# pow3_5e2.net
KiCad netlist of a schematic drawn in EAGLE
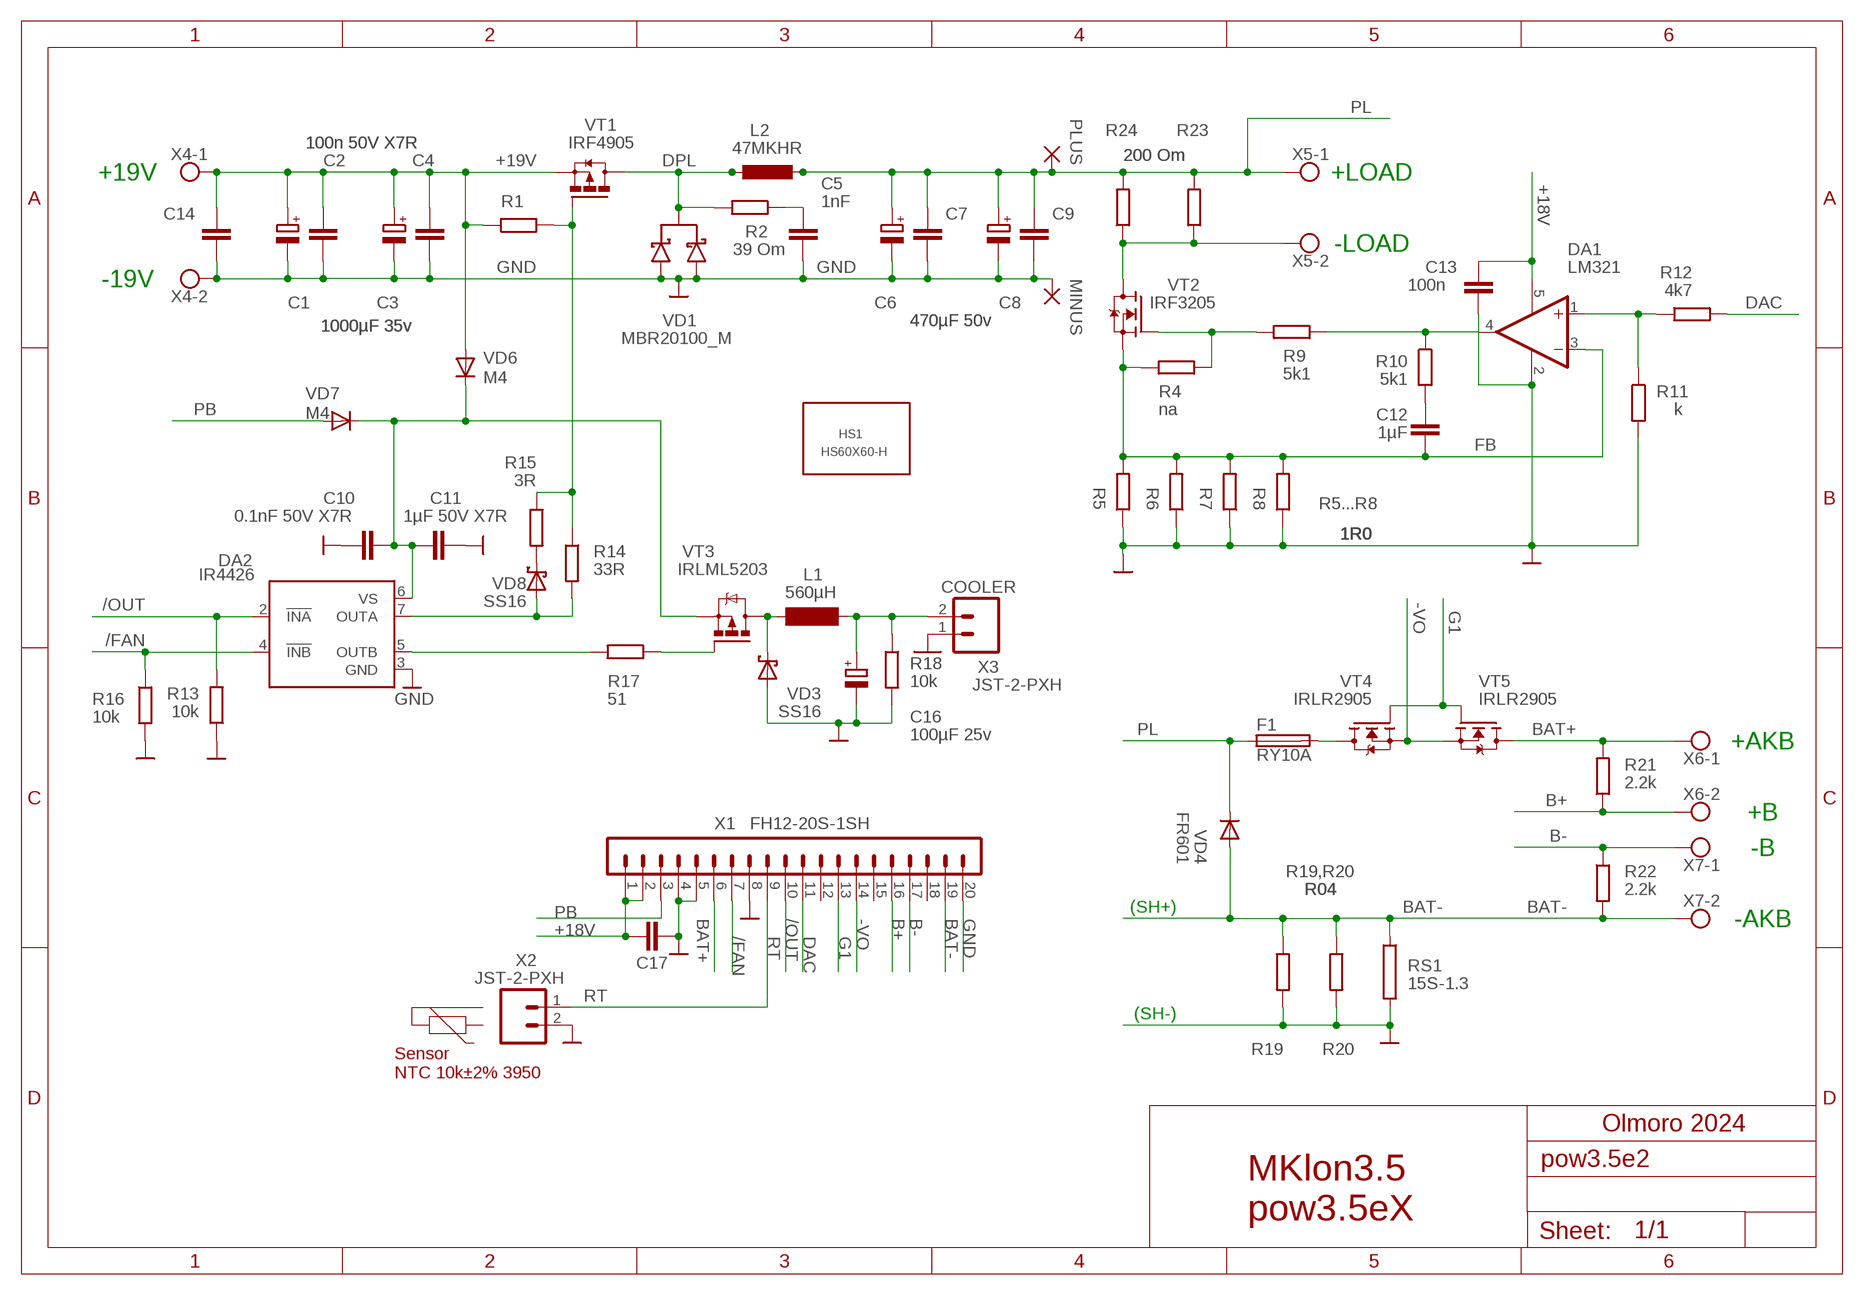
[diagram p0: schematic, sheet 1]

(export (version "E")
  (design (tool "Eeschema 10.0.6"))
  (components
    (comp (ref "C1")
      (value "1000µF 35v")
      (footprint "eagle-import:E5-10,5")
      (libsource (lib "eagle-import") (part "CPOL-EUE5-10.5"))
    )
    (comp (ref "C2")
      (value "100n 50V X7R")
      (footprint "eagle-import:C0805")
      (libsource (lib "eagle-import") (part "C-EUC0805"))
    )
    (comp (ref "C3")
      (value "1000µF 35v")
      (footprint "eagle-import:E5-10,5")
      (libsource (lib "eagle-import") (part "CPOL-EUE5-10.5"))
    )
    (comp (ref "C4")
      (value "100n 50V X7R")
      (footprint "eagle-import:C0805")
      (libsource (lib "eagle-import") (part "C-EUC0805"))
    )
    (comp (ref "C5")
      (value "1nF")
      (footprint "eagle-import:C075-042X103")
      (libsource (lib "eagle-import") (part "C-EU075-042X103"))
    )
    (comp (ref "C6")
      (value "470µF 50v")
      (footprint "eagle-import:E5-10,5")
      (libsource (lib "eagle-import") (part "CPOL-EUE5-10.5"))
    )
    (comp (ref "C7")
      (value "1mkF 50V X7R")
      (footprint "eagle-import:C0805")
      (libsource (lib "eagle-import") (part "C-EUC0805"))
    )
    (comp (ref "C8")
      (value "470µF 50v")
      (footprint "eagle-import:E5-10,5")
      (libsource (lib "eagle-import") (part "CPOL-EUE5-10.5"))
    )
    (comp (ref "C9")
      (value "1mkF 50V X7R")
      (footprint "eagle-import:C0805")
      (libsource (lib "eagle-import") (part "C-EUC0805"))
    )
    (comp (ref "C10")
      (value "0.1nF 50V X7R")
      (footprint "eagle-import:C0805")
      (libsource (lib "eagle-import") (part "C-EUC0805"))
    )
    (comp (ref "C11")
      (value "1µF 50V X7R")
      (footprint "eagle-import:C0805")
      (libsource (lib "eagle-import") (part "C-EUC0805"))
    )
    (comp (ref "C12")
      (value "1µF")
      (footprint "eagle-import:C0805")
      (libsource (lib "eagle-import") (part "C-EUC0805"))
    )
    (comp (ref "C13")
      (value "100n")
      (footprint "eagle-import:C0805")
      (libsource (lib "eagle-import") (part "C-EUC0805"))
    )
    (comp (ref "C14")
      (value "1mkF 50V X7R")
      (footprint "eagle-import:C0805")
      (libsource (lib "eagle-import") (part "C-EUC0805"))
    )
    (comp (ref "C16")
      (value "100µF 25v")
      (footprint "eagle-import:E5-6")
      (libsource (lib "eagle-import") (part "CPOL-EUE5-6"))
    )
    (comp (ref "C17")
      (value "C-EUC0805")
      (footprint "eagle-import:C0805")
      (libsource (lib "eagle-import") (part "C-EUC0805"))
    )
    (comp (ref "DA1")
      (value "LM321")
      (footprint "eagle-import:SOT23-5")
      (libsource (lib "eagle-import") (part "LM321?MF"))
    )
    (comp (ref "DA2")
      (value "IR4426")
      (footprint "eagle-import:DIL08")
      (fields (field (name "MF") "INTERNATIONAL RECTIFIER(IR)") (field (name "MPN") "IR4426PBF"))
      (libsource (lib "eagle-import") (part "IR4426"))
    )
    (comp (ref "F1")
      (value "RY10A")
      (footprint "eagle-import:RY10A")
      (libsource (lib "eagle-import") (part "RY10A"))
    )
    (comp (ref "HS1")
      (value "HS60X60-H")
      (footprint "eagle-import:HS60X60-H")
      (libsource (lib "eagle-import") (part "HS60X60-H"))
    )
    (comp (ref "L1")
      (value "560µH")
      (footprint "eagle-import:BS11")
      (libsource (lib "eagle-import") (part "BS11"))
    )
    (comp (ref "L2")
      (value "47MKHR")
      (footprint "eagle-import:47MKHR")
      (libsource (lib "eagle-import") (part "47MKHR"))
    )
    (comp (ref "MINUS")
      (value "3,81/1,4")
      (footprint "eagle-import:3,81_1,4")
      (libsource (lib "eagle-import") (part "3,81/1,4"))
    )
    (comp (ref "PLUS")
      (value "3,81/1,4")
      (footprint "eagle-import:3,81_1,4")
      (libsource (lib "eagle-import") (part "3,81/1,4"))
    )
    (comp (ref "R1")
      (value "R-EU_R1206")
      (footprint "eagle-import:R1206")
      (libsource (lib "eagle-import") (part "R-EU_R1206"))
    )
    (comp (ref "R2")
      (value "39 Om")
      (footprint "eagle-import:0414_15")
      (libsource (lib "eagle-import") (part "R-EU_0414/15"))
    )
    (comp (ref "R4")
      (value "na")
      (footprint "eagle-import:R1206")
      (libsource (lib "eagle-import") (part "R-EU_R1206"))
    )
    (comp (ref "R5")
      (value "1R0")
      (footprint "eagle-import:R2512")
      (libsource (lib "eagle-import") (part "R-EU_R2512"))
    )
    (comp (ref "R6")
      (value "1R0")
      (footprint "eagle-import:R2512")
      (libsource (lib "eagle-import") (part "R-EU_R2512"))
    )
    (comp (ref "R7")
      (value "1R0")
      (footprint "eagle-import:R2512")
      (libsource (lib "eagle-import") (part "R-EU_R2512"))
    )
    (comp (ref "R8")
      (value "1R0")
      (footprint "eagle-import:R2512")
      (libsource (lib "eagle-import") (part "R-EU_R2512"))
    )
    (comp (ref "R9")
      (value "5k1")
      (footprint "eagle-import:R0805")
      (libsource (lib "eagle-import") (part "R-EU_R0805"))
    )
    (comp (ref "R10")
      (value "5k1")
      (footprint "eagle-import:R0805")
      (libsource (lib "eagle-import") (part "R-EU_R0805"))
    )
    (comp (ref "R11")
      (value "k")
      (footprint "eagle-import:R0805")
      (libsource (lib "eagle-import") (part "R-EU_R0805"))
    )
    (comp (ref "R12")
      (value "4k7")
      (footprint "eagle-import:R0805")
      (libsource (lib "eagle-import") (part "R-EU_R0805"))
    )
    (comp (ref "R13")
      (value "10k")
      (footprint "eagle-import:R0805")
      (libsource (lib "eagle-import") (part "R-EU_R0805"))
    )
    (comp (ref "R14")
      (value "33R")
      (footprint "eagle-import:R1206")
      (libsource (lib "eagle-import") (part "R-EU_R1206"))
    )
    (comp (ref "R15")
      (value "3R")
      (footprint "eagle-import:R1206")
      (libsource (lib "eagle-import") (part "R-EU_R1206"))
    )
    (comp (ref "R16")
      (value "10k")
      (footprint "eagle-import:R0805")
      (libsource (lib "eagle-import") (part "R-EU_R0805"))
    )
    (comp (ref "R17")
      (value "51")
      (footprint "eagle-import:R0805")
      (libsource (lib "eagle-import") (part "R-EU_R0805"))
    )
    (comp (ref "R18")
      (value "10k")
      (footprint "eagle-import:R0805")
      (libsource (lib "eagle-import") (part "R-EU_R0805"))
    )
    (comp (ref "R19")
      (value "R04")
      (footprint "eagle-import:R2512")
      (libsource (lib "eagle-import") (part "R-EU_R2512"))
    )
    (comp (ref "R20")
      (value "R04")
      (footprint "eagle-import:R2512")
      (libsource (lib "eagle-import") (part "R-EU_R2512"))
    )
    (comp (ref "R21")
      (value "2.2k")
      (footprint "eagle-import:R1206")
      (libsource (lib "eagle-import") (part "R-EU_R1206"))
    )
    (comp (ref "R22")
      (value "2.2k")
      (footprint "eagle-import:R1206")
      (libsource (lib "eagle-import") (part "R-EU_R1206"))
    )
    (comp (ref "R23")
      (value "200 Om")
      (footprint "eagle-import:0414_15")
      (libsource (lib "eagle-import") (part "R-EU_0414/15"))
    )
    (comp (ref "R24")
      (value "200 Om")
      (footprint "eagle-import:0414_15")
      (libsource (lib "eagle-import") (part "R-EU_0414/15"))
    )
    (comp (ref "RS1")
      (value "15S-1.3")
      (footprint "eagle-import:15S-1.3")
      (libsource (lib "eagle-import") (part "15S-1.3"))
    )
    (comp (ref "VD1")
      (value "MBR20100_M")
      (footprint "eagle-import:TO220DLK")
      (libsource (lib "eagle-import") (part "MBR20100_M"))
    )
    (comp (ref "VD3")
      (value "SS16")
      (footprint "eagle-import:DO214AC")
      (libsource (lib "eagle-import") (part "SS16"))
    )
    (comp (ref "VD4")
      (value "FR601")
      (footprint "eagle-import:DIODE-1_P6-15")
      (libsource (lib "eagle-import") (part "DIODE-1_DIODE-P6-15"))
    )
    (comp (ref "VD6")
      (value "M4")
      (footprint "eagle-import:DO214AC")
      (libsource (lib "eagle-import") (part "DIODE-DO214AC"))
    )
    (comp (ref "VD7")
      (value "M4")
      (footprint "eagle-import:DO214AC")
      (libsource (lib "eagle-import") (part "DIODE-DO214AC"))
    )
    (comp (ref "VD8")
      (value "SS16")
      (footprint "eagle-import:DO214AC")
      (libsource (lib "eagle-import") (part "SS16"))
    )
    (comp (ref "VT1")
      (value "IRF4905")
      (footprint "eagle-import:TO-220FP_M")
      (libsource (lib "eagle-import") (part "IRFP9540N_M"))
    )
    (comp (ref "VT2")
      (value "IRF3205")
      (footprint "eagle-import:TO-220FP_M")
      (libsource (lib "eagle-import") (part "STP16NF06FP"))
    )
    (comp (ref "VT3")
      (value "IRLML5203")
      (footprint "eagle-import:MICRO3")
      (libsource (lib "eagle-import") (part "IRLML5203"))
    )
    (comp (ref "VT4")
      (value "IRLR2905")
      (footprint "eagle-import:TO252")
      (libsource (lib "eagle-import") (part "IRLR2905"))
    )
    (comp (ref "VT5")
      (value "IRLR2905")
      (footprint "eagle-import:TO252")
      (libsource (lib "eagle-import") (part "IRLR2905"))
    )
    (comp (ref "X1")
      (value "FH12-20S-1SH")
      (footprint "eagle-import:FH12-20S-1SH")
      (libsource (lib "eagle-import") (part "FH12-20S-1SH"))
    )
    (comp (ref "X2")
      (value "JST-2-PXH")
      (footprint "eagle-import:JST-2-PXH")
      (libsource (lib "eagle-import") (part "JST-2-PXH"))
    )
    (comp (ref "X3")
      (value "JST-2-PXH")
      (footprint "eagle-import:JST-2-PXH")
      (libsource (lib "eagle-import") (part "JST-2-PXH"))
    )
    (comp (ref "X4")
      (value "AK500/2")
      (footprint "eagle-import:AK500_2")
      (libsource (lib "eagle-import") (part "AK500/2"))
    )
    (comp (ref "X5")
      (value "AK500/2")
      (footprint "eagle-import:AK500_2")
      (libsource (lib "eagle-import") (part "AK500/2"))
    )
    (comp (ref "X6")
      (value "AK500/2")
      (footprint "eagle-import:AK500_2")
      (libsource (lib "eagle-import") (part "AK500/2"))
    )
    (comp (ref "X7")
      (value "AK500/2")
      (footprint "eagle-import:AK500_2")
      (libsource (lib "eagle-import") (part "AK500/2"))
    )
  )
  (nets
    (net (code "1") (name "/+18V") (class "Default")
      (node (ref "C13") (pin "2") (pinfunction "2_2") (pintype "passive"))
      (node (ref "C17") (pin "2") (pinfunction "2_2") (pintype "passive"))
      (node (ref "DA1") (pin "5") (pinfunction "V+_5") (pintype "power_in"))
      (node (ref "X1") (pin "1") (pinfunction "1_1") (pintype "passive"))
      (node (ref "X1") (pin "2") (pinfunction "2_2") (pintype "passive"))
    )
    (net (code "2") (name "/+19V") (class "Default")
      (node (ref "C1") (pin "+") (pinfunction "+_+") (pintype "passive"))
      (node (ref "C14") (pin "1") (pinfunction "1_1") (pintype "passive"))
      (node (ref "C2") (pin "2") (pinfunction "2_2") (pintype "passive"))
      (node (ref "C3") (pin "+") (pinfunction "+_+") (pintype "passive"))
      (node (ref "C4") (pin "2") (pinfunction "2_2") (pintype "passive"))
      (node (ref "R1") (pin "1") (pinfunction "1_1") (pintype "passive"))
      (node (ref "VD6") (pin "A") (pinfunction "A_A") (pintype "passive"))
      (node (ref "VT1") (pin "3") (pinfunction "S_3") (pintype "passive"))
      (node (ref "X4") (pin "1") (pinfunction "KL_1") (pintype "passive"))
    )
    (net (code "3") (name "/-VO") (class "Default")
      (node (ref "VT4") (pin "3") (pinfunction "S_3") (pintype "passive"))
      (node (ref "VT5") (pin "3") (pinfunction "S_3") (pintype "passive"))
      (node (ref "X1") (pin "14") (pinfunction "14_14") (pintype "passive"))
    )
    (net (code "4") (name "/B+") (class "Default")
      (node (ref "R21") (pin "1") (pinfunction "1_1") (pintype "passive"))
      (node (ref "X1") (pin "16") (pinfunction "16_16") (pintype "passive"))
      (node (ref "X6") (pin "2") (pinfunction "KL_2") (pintype "passive"))
    )
    (net (code "5") (name "/B-") (class "Default")
      (node (ref "R22") (pin "1") (pinfunction "1_1") (pintype "passive"))
      (node (ref "X1") (pin "17") (pinfunction "17_17") (pintype "passive"))
      (node (ref "X7") (pin "1") (pinfunction "KL_1") (pintype "passive"))
    )
    (net (code "6") (name "/BAT+") (class "Default")
      (node (ref "R21") (pin "2") (pinfunction "2_2") (pintype "passive"))
      (node (ref "VT5") (pin "4") (pinfunction "D_4") (pintype "passive"))
      (node (ref "X1") (pin "6") (pinfunction "6_6") (pintype "passive"))
      (node (ref "X6") (pin "1") (pinfunction "KL_1") (pintype "passive"))
    )
    (net (code "7") (name "/BAT-") (class "Default")
      (node (ref "R19") (pin "1") (pinfunction "1_1") (pintype "passive"))
      (node (ref "R20") (pin "1") (pinfunction "1_1") (pintype "passive"))
      (node (ref "R22") (pin "2") (pinfunction "2_2") (pintype "passive"))
      (node (ref "RS1") (pin "1") (pinfunction "1_1") (pintype "passive"))
      (node (ref "VD4") (pin "A") (pinfunction "A_A") (pintype "passive"))
      (node (ref "X1") (pin "19") (pinfunction "19_19") (pintype "passive"))
      (node (ref "X7") (pin "2") (pinfunction "KL_2") (pintype "passive"))
    )
    (net (code "8") (name "/COOLER") (class "Default")
      (node (ref "C16") (pin "+") (pinfunction "+_+") (pintype "passive"))
      (node (ref "L1") (pin "2") (pinfunction "2_2") (pintype "passive"))
      (node (ref "R18") (pin "1") (pinfunction "1_1") (pintype "passive"))
      (node (ref "X3") (pin "2") (pinfunction "2_2") (pintype "passive"))
    )
    (net (code "9") (name "/DAC") (class "Default")
      (node (ref "R12") (pin "2") (pinfunction "2_2") (pintype "passive"))
      (node (ref "X1") (pin "11") (pinfunction "11_11") (pintype "passive"))
    )
    (net (code "10") (name "/DPL") (class "Default")
      (node (ref "L2") (pin "1") (pinfunction "1_1") (pintype "passive"))
      (node (ref "L2") (pin "1@2") (pinfunction "1_1@2") (pintype "passive"))
      (node (ref "R2") (pin "2") (pinfunction "2_2") (pintype "passive"))
      (node (ref "VD1") (pin "2") (pinfunction "C_2") (pintype "passive"))
      (node (ref "VT1") (pin "2") (pinfunction "D_2") (pintype "passive"))
    )
    (net (code "11") (name "/FB") (class "Default")
      (node (ref "C12") (pin "2") (pinfunction "2_2") (pintype "passive"))
      (node (ref "DA1") (pin "3") (pinfunction "-IN_3") (pintype "input"))
      (node (ref "R4") (pin "1") (pinfunction "1_1") (pintype "passive"))
      (node (ref "R5") (pin "2") (pinfunction "2_2") (pintype "passive"))
      (node (ref "R6") (pin "2") (pinfunction "2_2") (pintype "passive"))
      (node (ref "R7") (pin "2") (pinfunction "2_2") (pintype "passive"))
      (node (ref "R8") (pin "2") (pinfunction "2_2") (pintype "passive"))
      (node (ref "VT2") (pin "3") (pinfunction "S_3") (pintype "passive"))
    )
    (net (code "12") (name "/G1") (class "Default")
      (node (ref "VT4") (pin "1") (pinfunction "G_1") (pintype "passive"))
      (node (ref "VT5") (pin "1") (pinfunction "G_1") (pintype "passive"))
      (node (ref "X1") (pin "13") (pinfunction "13_13") (pintype "passive"))
    )
    (net (code "13") (name "/PB") (class "Default")
      (node (ref "VD7") (pin "A") (pinfunction "A_A") (pintype "passive"))
      (node (ref "X1") (pin "3") (pinfunction "3_3") (pintype "passive"))
    )
    (net (code "14") (name "/PL") (class "Default")
      (node (ref "C6") (pin "+") (pinfunction "+_+") (pintype "passive"))
      (node (ref "C7") (pin "1") (pinfunction "1_1") (pintype "passive"))
      (node (ref "C8") (pin "+") (pinfunction "+_+") (pintype "passive"))
      (node (ref "C9") (pin "1") (pinfunction "1_1") (pintype "passive"))
      (node (ref "F1") (pin "1") (pinfunction "1_1") (pintype "passive"))
      (node (ref "L2") (pin "2@7") (pinfunction "2_2@7") (pintype "passive"))
      (node (ref "L2") (pin "2@8") (pinfunction "2_2@8") (pintype "passive"))
      (node (ref "PLUS") (pin "1") (pinfunction "P_1") (pintype "passive"))
      (node (ref "R23") (pin "2") (pinfunction "2_2") (pintype "passive"))
      (node (ref "R24") (pin "2") (pinfunction "2_2") (pintype "passive"))
      (node (ref "VD4") (pin "C") (pinfunction "C_C") (pintype "passive"))
      (node (ref "X5") (pin "1") (pinfunction "KL_1") (pintype "passive"))
    )
    (net (code "15") (name "/RT") (class "Default")
      (node (ref "X1") (pin "9") (pinfunction "9_9") (pintype "passive"))
      (node (ref "X2") (pin "1") (pinfunction "1_1") (pintype "passive"))
    )
    (net (code "16") (name "/{slash}FAN") (class "Default")
      (node (ref "DA2") (pin "4") (pinfunction "~{INB}_4") (pintype "input"))
      (node (ref "R16") (pin "1") (pinfunction "1_1") (pintype "passive"))
      (node (ref "X1") (pin "7") (pinfunction "7_7") (pintype "passive"))
    )
    (net (code "17") (name "/{slash}OUT") (class "Default")
      (node (ref "DA2") (pin "2") (pinfunction "~{INA}_2") (pintype "input"))
      (node (ref "R13") (pin "2") (pinfunction "2_2") (pintype "passive"))
      (node (ref "X1") (pin "10") (pinfunction "10_10") (pintype "passive"))
    )
    (net (code "18") (name "GND") (class "Default")
      (node (ref "C1") (pin "-") (pinfunction "-_-") (pintype "passive"))
      (node (ref "C10") (pin "1") (pinfunction "1_1") (pintype "passive"))
      (node (ref "C11") (pin "1") (pinfunction "1_1") (pintype "passive"))
      (node (ref "C13") (pin "1") (pinfunction "1_1") (pintype "passive"))
      (node (ref "C14") (pin "2") (pinfunction "2_2") (pintype "passive"))
      (node (ref "C16") (pin "-") (pinfunction "-_-") (pintype "passive"))
      (node (ref "C17") (pin "1") (pinfunction "1_1") (pintype "passive"))
      (node (ref "C2") (pin "1") (pinfunction "1_1") (pintype "passive"))
      (node (ref "C3") (pin "-") (pinfunction "-_-") (pintype "passive"))
      (node (ref "C4") (pin "1") (pinfunction "1_1") (pintype "passive"))
      (node (ref "C5") (pin "2") (pinfunction "2_2") (pintype "passive"))
      (node (ref "C6") (pin "-") (pinfunction "-_-") (pintype "passive"))
      (node (ref "C7") (pin "2") (pinfunction "2_2") (pintype "passive"))
      (node (ref "C8") (pin "-") (pinfunction "-_-") (pintype "passive"))
      (node (ref "C9") (pin "2") (pinfunction "2_2") (pintype "passive"))
      (node (ref "DA1") (pin "2") (pinfunction "V-_2") (pintype "power_in"))
      (node (ref "DA2") (pin "3") (pinfunction "GND_3") (pintype "power_in"))
      (node (ref "MINUS") (pin "1") (pinfunction "P_1") (pintype "passive"))
      (node (ref "R11") (pin "2") (pinfunction "2_2") (pintype "passive"))
      (node (ref "R13") (pin "1") (pinfunction "1_1") (pintype "passive"))
      (node (ref "R16") (pin "2") (pinfunction "2_2") (pintype "passive"))
      (node (ref "R18") (pin "2") (pinfunction "2_2") (pintype "passive"))
      (node (ref "R19") (pin "2") (pinfunction "2_2") (pintype "passive"))
      (node (ref "R20") (pin "2") (pinfunction "2_2") (pintype "passive"))
      (node (ref "R5") (pin "1") (pinfunction "1_1") (pintype "passive"))
      (node (ref "R6") (pin "1") (pinfunction "1_1") (pintype "passive"))
      (node (ref "R7") (pin "1") (pinfunction "1_1") (pintype "passive"))
      (node (ref "R8") (pin "1") (pinfunction "1_1") (pintype "passive"))
      (node (ref "RS1") (pin "2") (pinfunction "2_2") (pintype "passive"))
      (node (ref "VD1") (pin "1") (pinfunction "A1_1") (pintype "passive"))
      (node (ref "VD1") (pin "3") (pinfunction "A2_3") (pintype "passive"))
      (node (ref "VD3") (pin "A") (pinfunction "A_A") (pintype "passive"))
      (node (ref "X1") (pin "20") (pinfunction "20_20") (pintype "passive"))
      (node (ref "X1") (pin "4") (pinfunction "4_4") (pintype "passive"))
      (node (ref "X1") (pin "5") (pinfunction "5_5") (pintype "passive"))
      (node (ref "X1") (pin "8") (pinfunction "8_8") (pintype "passive"))
      (node (ref "X2") (pin "2") (pinfunction "2_2") (pintype "passive"))
      (node (ref "X3") (pin "1") (pinfunction "1_1") (pintype "passive"))
      (node (ref "X4") (pin "2") (pinfunction "KL_2") (pintype "passive"))
    )
    (net (code "19") (name "Net-(C5-Pad1)") (class "Default")
      (node (ref "C5") (pin "1") (pinfunction "1_1") (pintype "passive"))
      (node (ref "R2") (pin "1") (pinfunction "1_1") (pintype "passive"))
    )
    (net (code "20") (name "Net-(C12-Pad1)") (class "Default")
      (node (ref "C12") (pin "1") (pinfunction "1_1") (pintype "passive"))
      (node (ref "R10") (pin "2") (pinfunction "2_2") (pintype "passive"))
    )
    (net (code "21") (name "Net-(DA1-+IN)") (class "Default")
      (node (ref "DA1") (pin "1") (pinfunction "+IN_1") (pintype "input"))
      (node (ref "R11") (pin "1") (pinfunction "1_1") (pintype "passive"))
      (node (ref "R12") (pin "1") (pinfunction "1_1") (pintype "passive"))
    )
    (net (code "22") (name "Net-(DA1-OUT)") (class "Default")
      (node (ref "DA1") (pin "4") (pinfunction "OUT_4") (pintype "output"))
      (node (ref "R10") (pin "1") (pinfunction "1_1") (pintype "passive"))
      (node (ref "R9") (pin "1") (pinfunction "1_1") (pintype "passive"))
    )
    (net (code "23") (name "Net-(DA2-OUTA)") (class "Default")
      (node (ref "DA2") (pin "7") (pinfunction "OUTA_7") (pintype "output"))
      (node (ref "R14") (pin "2") (pinfunction "2_2") (pintype "passive"))
      (node (ref "VD8") (pin "A") (pinfunction "A_A") (pintype "passive"))
    )
    (net (code "24") (name "Net-(DA2-OUTB)") (class "Default")
      (node (ref "DA2") (pin "5") (pinfunction "OUTB_5") (pintype "output"))
      (node (ref "R17") (pin "2") (pinfunction "2_2") (pintype "passive"))
    )
    (net (code "25") (name "Net-(DA2-VS)") (class "Default")
      (node (ref "C10") (pin "2") (pinfunction "2_2") (pintype "passive"))
      (node (ref "C11") (pin "2") (pinfunction "2_2") (pintype "passive"))
      (node (ref "DA2") (pin "6") (pinfunction "VS_6") (pintype "power_in"))
      (node (ref "VD6") (pin "C") (pinfunction "C_C") (pintype "passive"))
      (node (ref "VD7") (pin "C") (pinfunction "C_C") (pintype "passive"))
      (node (ref "VT3") (pin "2") (pinfunction "S_2") (pintype "passive"))
    )
    (net (code "26") (name "Net-(R15-Pad2)") (class "Default")
      (node (ref "R15") (pin "2") (pinfunction "2_2") (pintype "passive"))
      (node (ref "VD8") (pin "C") (pinfunction "C_C") (pintype "passive"))
    )
    (net (code "27") (name "Net-(VT1-G)") (class "Default")
      (node (ref "R1") (pin "2") (pinfunction "2_2") (pintype "passive"))
      (node (ref "R14") (pin "1") (pinfunction "1_1") (pintype "passive"))
      (node (ref "R15") (pin "1") (pinfunction "1_1") (pintype "passive"))
      (node (ref "VT1") (pin "1") (pinfunction "G_1") (pintype "passive"))
    )
    (net (code "28") (name "Net-(VT2-D)") (class "Default")
      (node (ref "R23") (pin "1") (pinfunction "1_1") (pintype "passive"))
      (node (ref "R24") (pin "1") (pinfunction "1_1") (pintype "passive"))
      (node (ref "VT2") (pin "2") (pinfunction "D_2") (pintype "passive"))
      (node (ref "X5") (pin "2") (pinfunction "KL_2") (pintype "passive"))
    )
    (net (code "29") (name "Net-(VT2-G)") (class "Default")
      (node (ref "R4") (pin "2") (pinfunction "2_2") (pintype "passive"))
      (node (ref "R9") (pin "2") (pinfunction "2_2") (pintype "passive"))
      (node (ref "VT2") (pin "1") (pinfunction "G_1") (pintype "passive"))
    )
    (net (code "30") (name "Net-(VT3-D)") (class "Default")
      (node (ref "L1") (pin "1") (pinfunction "1_1") (pintype "passive"))
      (node (ref "VD3") (pin "C") (pinfunction "C_C") (pintype "passive"))
      (node (ref "VT3") (pin "3") (pinfunction "D_3") (pintype "passive"))
    )
    (net (code "31") (name "Net-(VT3-G)") (class "Default")
      (node (ref "R17") (pin "1") (pinfunction "1_1") (pintype "passive"))
      (node (ref "VT3") (pin "1") (pinfunction "G_1") (pintype "passive"))
    )
    (net (code "32") (name "Net-(VT4-D)") (class "Default")
      (node (ref "F1") (pin "2") (pinfunction "2_2") (pintype "passive"))
      (node (ref "VT4") (pin "4") (pinfunction "D_4") (pintype "passive"))
    )
    (net (code "33") (name "unconnected-(X1-Pad12)") (class "Default")
      (node (ref "X1") (pin "12") (pinfunction "12_12") (pintype "passive"))
    )
    (net (code "34") (name "unconnected-(X1-Pad15)") (class "Default")
      (node (ref "X1") (pin "15") (pinfunction "15_15") (pintype "passive"))
    )
    (net (code "35") (name "unconnected-(X1-Pad18)") (class "Default")
      (node (ref "X1") (pin "18") (pinfunction "18_18") (pintype "passive"))
    )
  )
)
